# LurkerNanov20.net
KiCad netlist of a schematic drawn in EAGLE
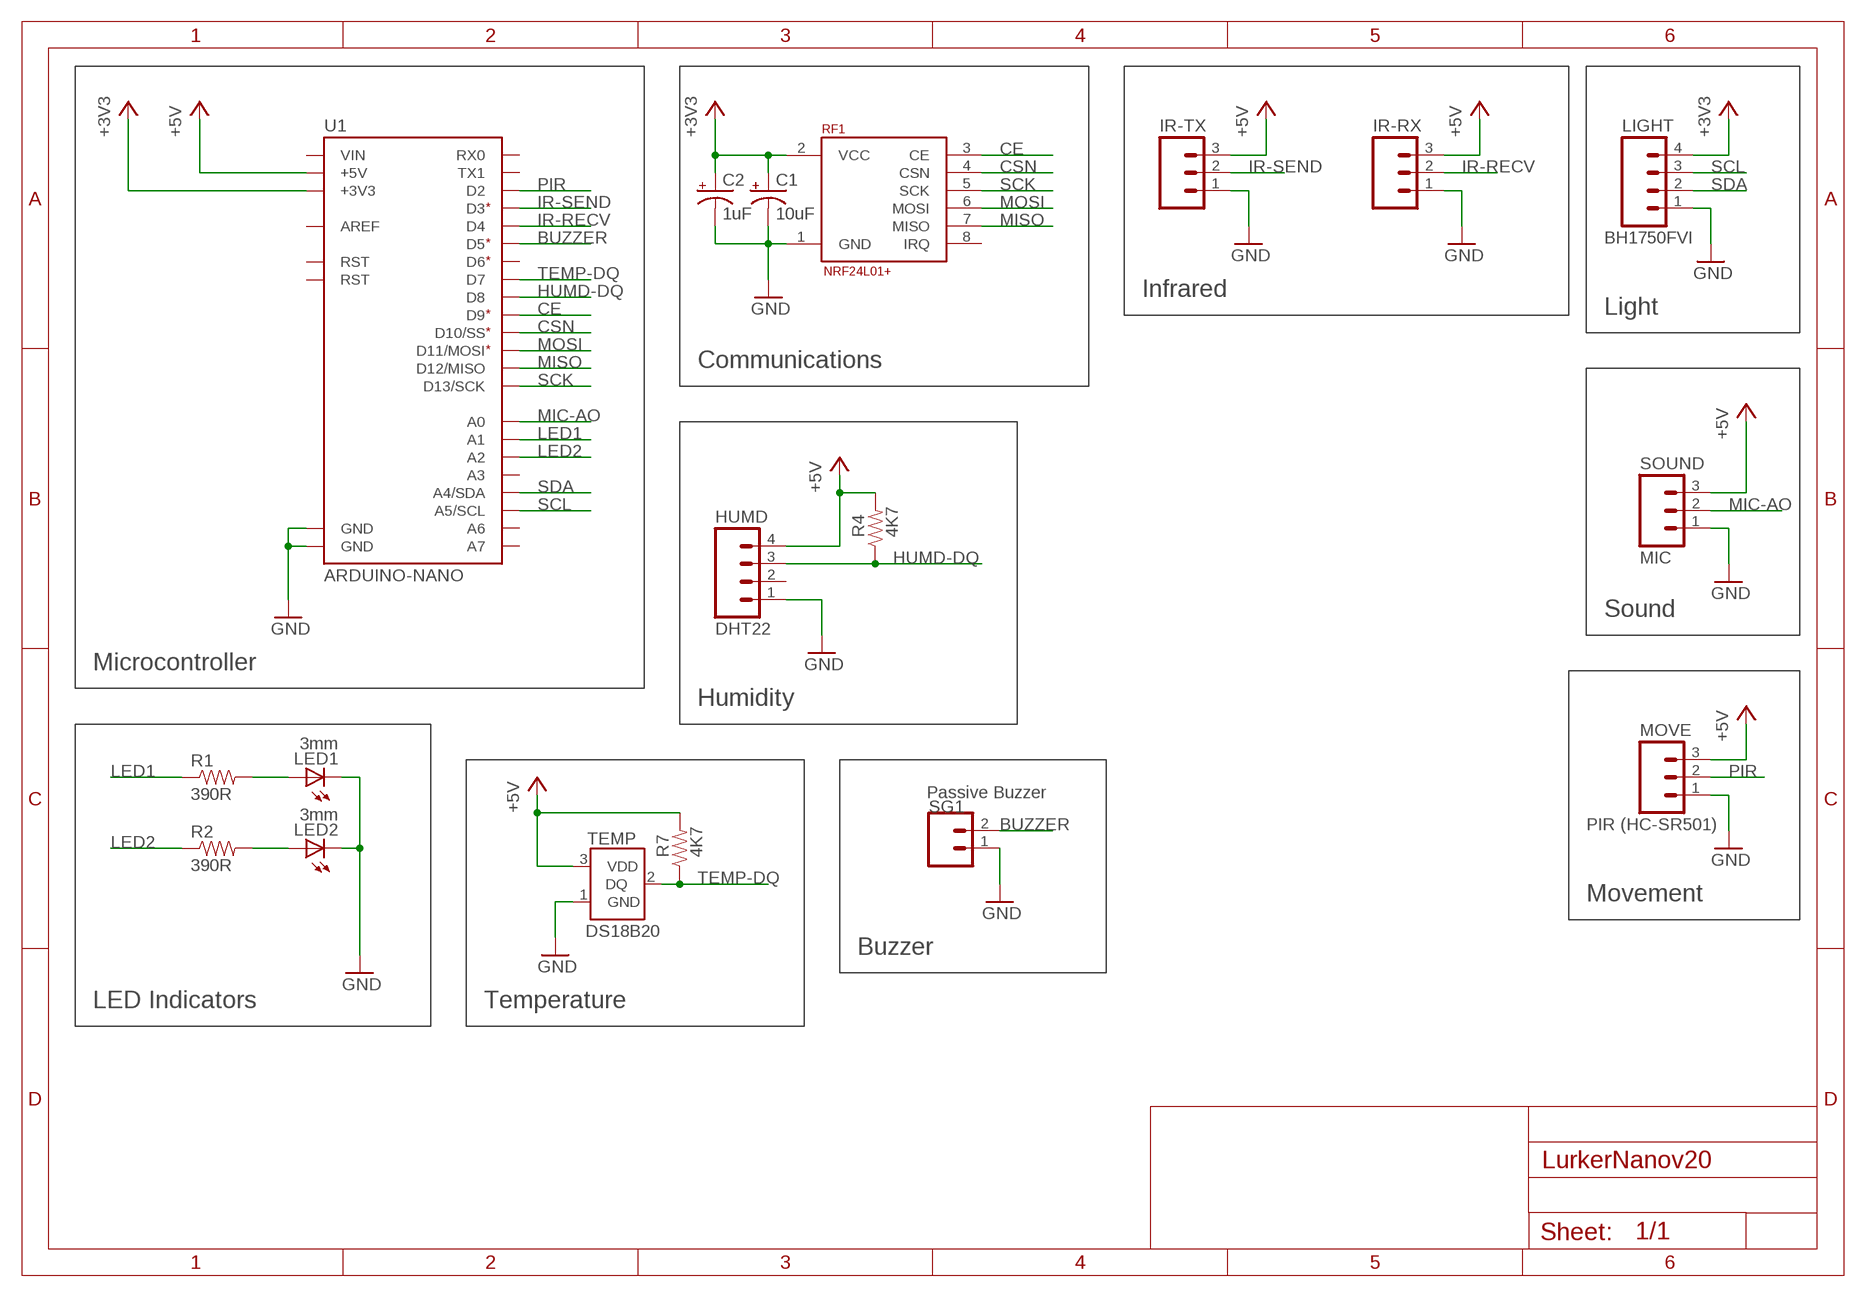
[diagram p0: schematic, sheet 1, part 1 of 2]
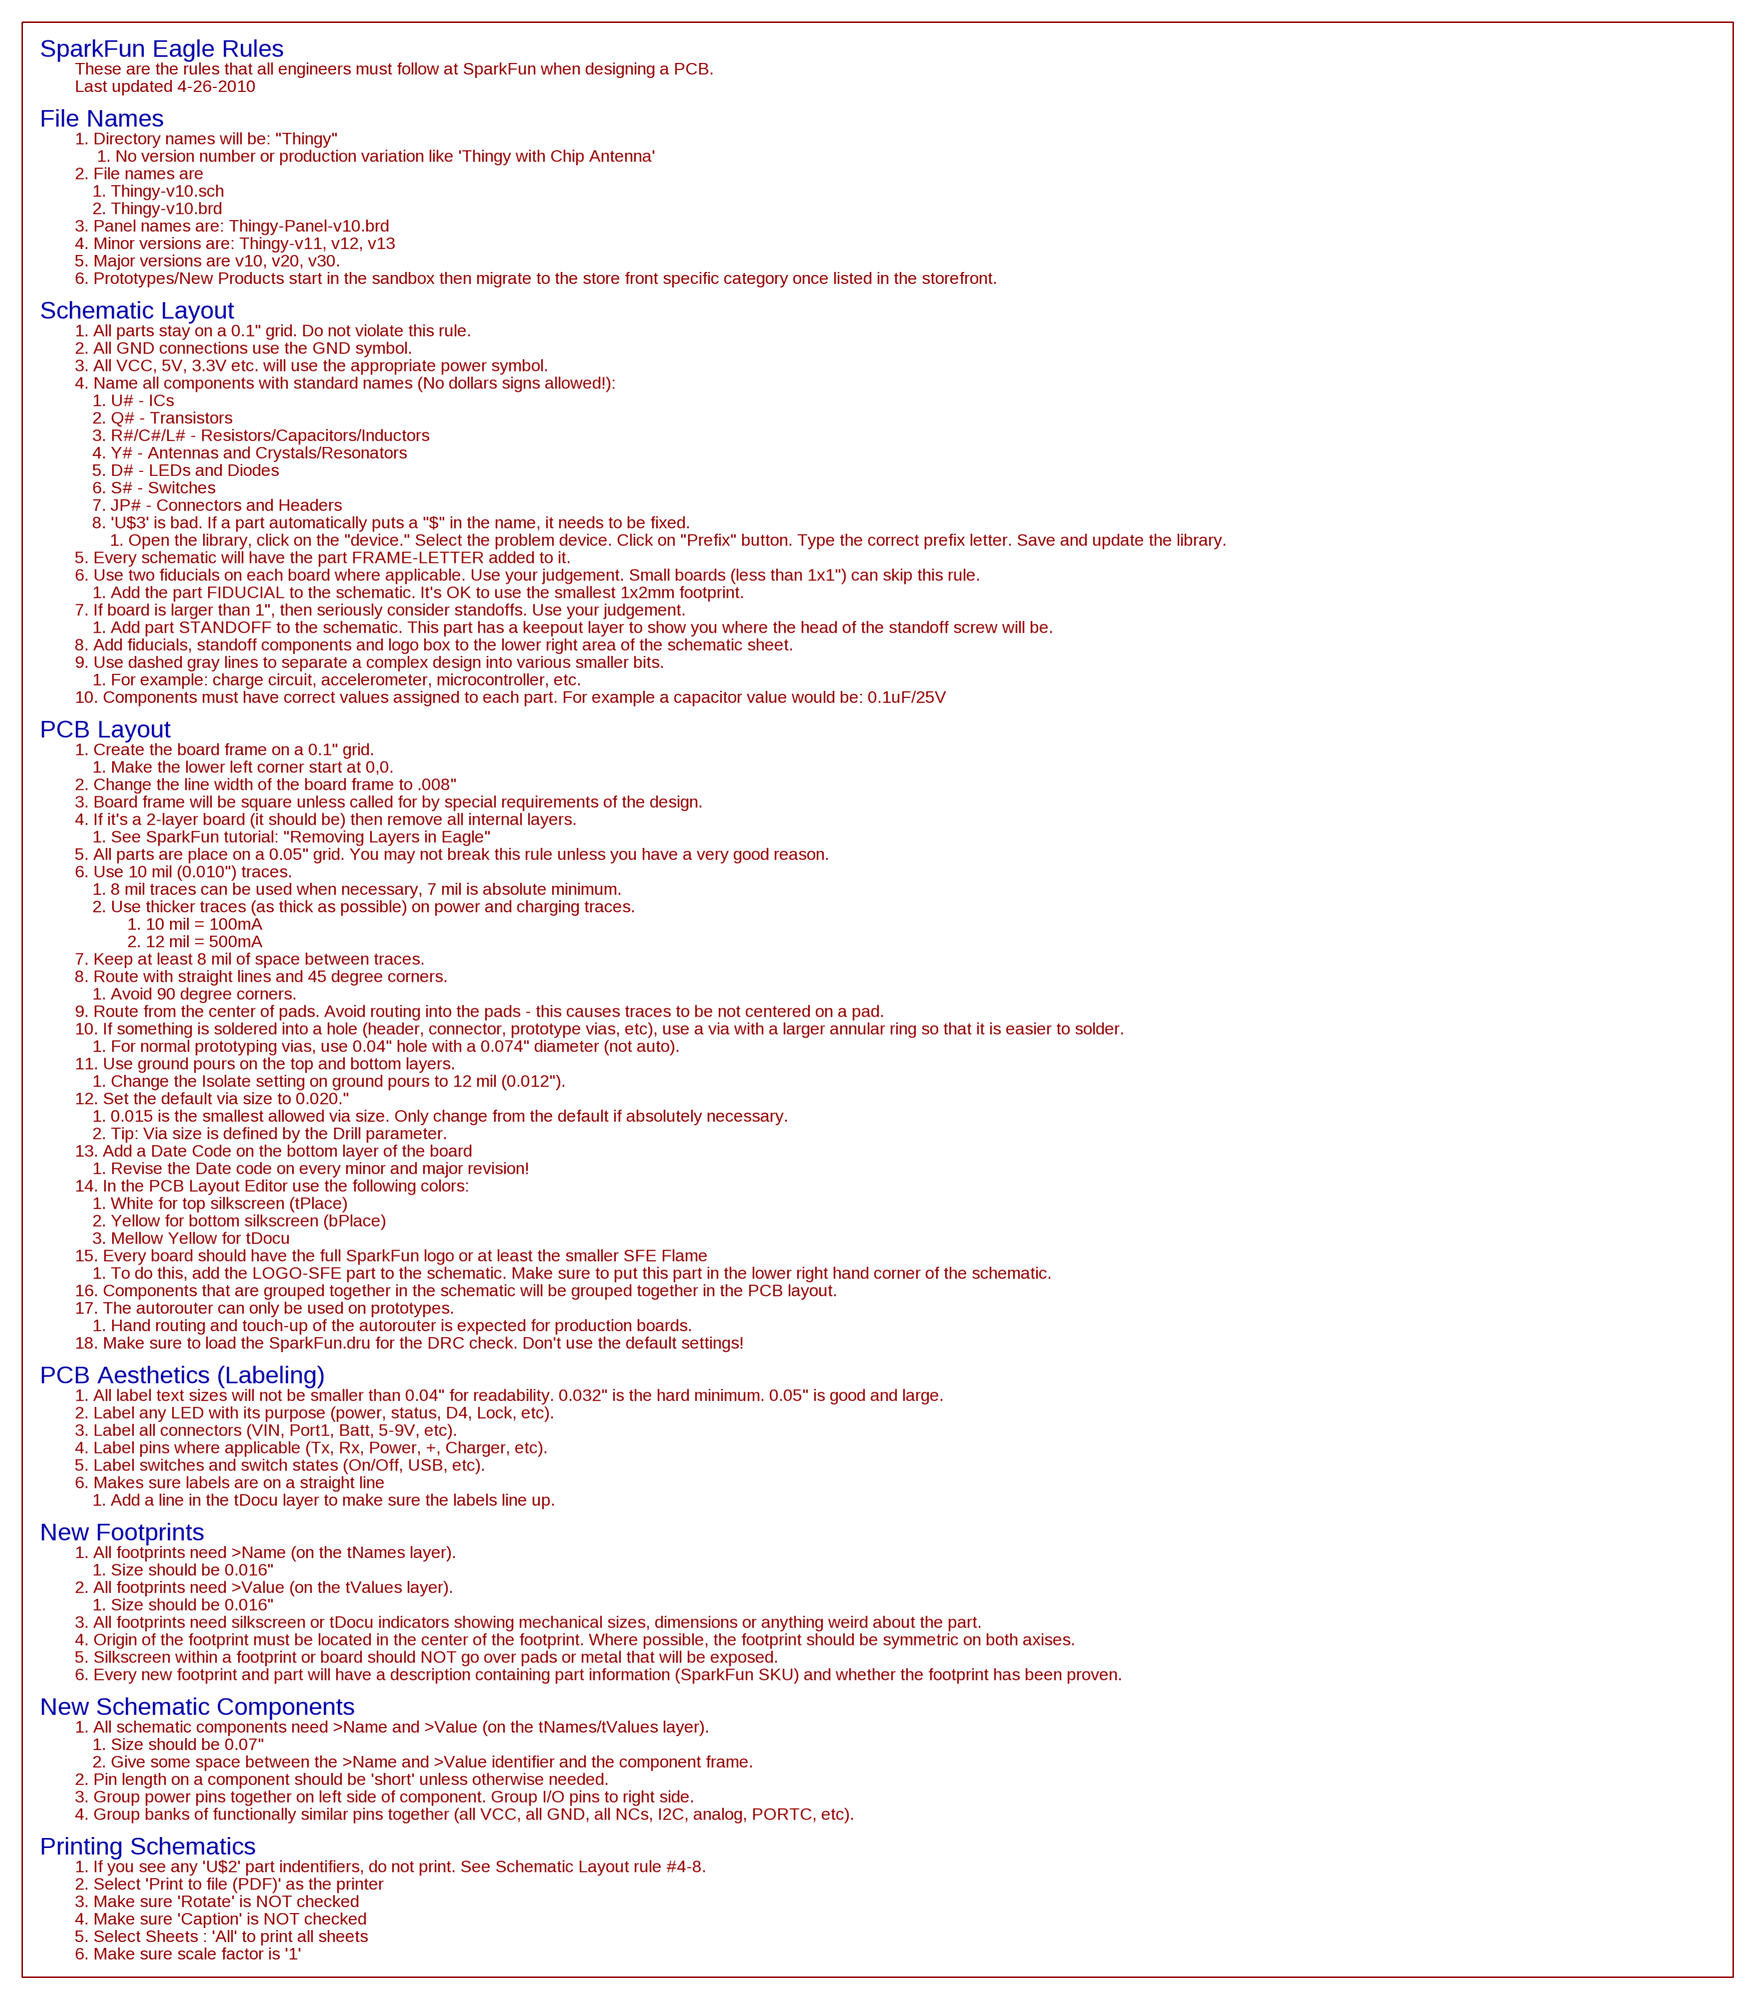
[diagram p1: schematic, sheet 1, part 2 of 2]

(export (version "E")
  (design (tool "Eeschema 10.0.6"))
  (components
    (comp (ref "C1")
      (value "10uF")
      (footprint "eagle-import:EIA3216")
      (libsource (lib "eagle-import") (part "CAP_POL1206"))
    )
    (comp (ref "C2")
      (value "1uF")
      (footprint "eagle-import:EIA3216")
      (libsource (lib "eagle-import") (part "CAP_POL1206"))
    )
    (comp (ref "HUMD")
      (value "DHT22")
      (footprint "eagle-import:1X04")
      (libsource (lib "eagle-import") (part "M04PTH"))
    )
    (comp (ref "IR-RX")
      (value "M03PTH")
      (footprint "eagle-import:1X03")
      (libsource (lib "eagle-import") (part "M03PTH"))
    )
    (comp (ref "IR-TX")
      (value "M03PTH")
      (footprint "eagle-import:1X03")
      (libsource (lib "eagle-import") (part "M03PTH"))
    )
    (comp (ref "LED1")
      (value "3mm")
      (footprint "eagle-import:LED3MM")
      (libsource (lib "eagle-import") (part "LED3MM"))
    )
    (comp (ref "LED2")
      (value "3mm")
      (footprint "eagle-import:LED3MM")
      (libsource (lib "eagle-import") (part "LED3MM"))
    )
    (comp (ref "LIGHT")
      (value "BH1750FVI")
      (footprint "eagle-import:1X04")
      (libsource (lib "eagle-import") (part "M04PTH"))
    )
    (comp (ref "MOVE")
      (value "PIR (HC-SR501)")
      (footprint "eagle-import:1X03")
      (libsource (lib "eagle-import") (part "M03PTH"))
    )
    (comp (ref "R1")
      (value "390R")
      (footprint "eagle-import:1206")
      (libsource (lib "eagle-import") (part "RESISTOR1206"))
    )
    (comp (ref "R2")
      (value "390R")
      (footprint "eagle-import:1206")
      (libsource (lib "eagle-import") (part "RESISTOR1206"))
    )
    (comp (ref "R4")
      (value "4K7")
      (footprint "eagle-import:1206")
      (libsource (lib "eagle-import") (part "RESISTOR1206"))
    )
    (comp (ref "R7")
      (value "4K7")
      (footprint "eagle-import:1206")
      (libsource (lib "eagle-import") (part "RESISTOR1206"))
    )
    (comp (ref "RF1")
      (value "NRF24L01+")
      (footprint "eagle-import:NRF24L01+-HEADER")
      (libsource (lib "eagle-import") (part "NRF24L01+"))
    )
    (comp (ref "SG1")
      (value "Passive Buzzer")
      (footprint "eagle-import:1X02")
      (libsource (lib "eagle-import") (part "M02PTH"))
    )
    (comp (ref "SOUND")
      (value "MIC")
      (footprint "eagle-import:1X03")
      (libsource (lib "eagle-import") (part "M03PTH"))
    )
    (comp (ref "TEMP")
      (value "DS18B20")
      (footprint "eagle-import:TO-92-AMMO")
      (libsource (lib "eagle-import") (part "DS18B20"))
    )
    (comp (ref "U1")
      (value "ARDUINO-NANO")
      (footprint "eagle-import:NANO-SHIELD")
      (libsource (lib "eagle-import") (part "ARDUINO-NANO"))
    )
  )
  (nets
    (net (code "1") (name "+3V3") (class "Default")
      (node (ref "C1") (pin "A") (pinfunction "+_A") (pintype "passive"))
      (node (ref "C2") (pin "A") (pinfunction "+_A") (pintype "passive"))
      (node (ref "LIGHT") (pin "4") (pinfunction "4_4") (pintype "passive"))
      (node (ref "RF1") (pin "2") (pinfunction "VCC_2") (pintype "power_in"))
      (node (ref "U1") (pin "3V3") (pinfunction "+3V3_3V3") (pintype "power_in"))
    )
    (net (code "2") (name "+5V") (class "Default")
      (node (ref "HUMD") (pin "4") (pinfunction "4_4") (pintype "passive"))
      (node (ref "IR-RX") (pin "3") (pinfunction "3_3") (pintype "passive"))
      (node (ref "IR-TX") (pin "3") (pinfunction "3_3") (pintype "passive"))
      (node (ref "MOVE") (pin "3") (pinfunction "3_3") (pintype "passive"))
      (node (ref "R4") (pin "2") (pinfunction "2_2") (pintype "passive"))
      (node (ref "R7") (pin "2") (pinfunction "2_2") (pintype "passive"))
      (node (ref "SOUND") (pin "3") (pinfunction "3_3") (pintype "passive"))
      (node (ref "TEMP") (pin "3") (pinfunction "VDD_3") (pintype "power_in"))
      (node (ref "U1") (pin "5V") (pinfunction "+5V_5V") (pintype "power_in"))
    )
    (net (code "3") (name "/BUZZER") (class "Default")
      (node (ref "SG1") (pin "2") (pinfunction "2_2") (pintype "passive"))
      (node (ref "U1") (pin "D5") (pinfunction "D5_D5") (pintype "bidirectional"))
    )
    (net (code "4") (name "/CE") (class "Default")
      (node (ref "RF1") (pin "3") (pinfunction "CE_3") (pintype "bidirectional"))
      (node (ref "U1") (pin "D9") (pinfunction "D9_D9") (pintype "bidirectional"))
    )
    (net (code "5") (name "/CSN") (class "Default")
      (node (ref "RF1") (pin "4") (pinfunction "CSN_4") (pintype "bidirectional"))
      (node (ref "U1") (pin "D10") (pinfunction "D10/SS_D10") (pintype "bidirectional"))
    )
    (net (code "6") (name "/HUMD-DQ") (class "Default")
      (node (ref "HUMD") (pin "3") (pinfunction "3_3") (pintype "passive"))
      (node (ref "R4") (pin "1") (pinfunction "1_1") (pintype "passive"))
      (node (ref "U1") (pin "D8") (pinfunction "D8_D8") (pintype "bidirectional"))
    )
    (net (code "7") (name "/IR-RECV") (class "Default")
      (node (ref "IR-RX") (pin "2") (pinfunction "2_2") (pintype "passive"))
      (node (ref "U1") (pin "D4") (pinfunction "D4_D4") (pintype "bidirectional"))
    )
    (net (code "8") (name "/IR-SEND") (class "Default")
      (node (ref "IR-TX") (pin "2") (pinfunction "2_2") (pintype "passive"))
      (node (ref "U1") (pin "D3") (pinfunction "D3_D3") (pintype "bidirectional"))
    )
    (net (code "9") (name "/LED1") (class "Default")
      (node (ref "R1") (pin "1") (pinfunction "1_1") (pintype "passive"))
      (node (ref "U1") (pin "A1") (pinfunction "A1_A1") (pintype "bidirectional"))
    )
    (net (code "10") (name "/LED2") (class "Default")
      (node (ref "R2") (pin "1") (pinfunction "1_1") (pintype "passive"))
      (node (ref "U1") (pin "A2") (pinfunction "A2_A2") (pintype "bidirectional"))
    )
    (net (code "11") (name "/MIC-AO") (class "Default")
      (node (ref "SOUND") (pin "2") (pinfunction "2_2") (pintype "passive"))
      (node (ref "U1") (pin "A0") (pinfunction "A0_A0") (pintype "bidirectional"))
    )
    (net (code "12") (name "/MISO") (class "Default")
      (node (ref "RF1") (pin "7") (pinfunction "MISO_7") (pintype "bidirectional"))
      (node (ref "U1") (pin "D12") (pinfunction "D12/MISO_D12") (pintype "bidirectional"))
    )
    (net (code "13") (name "/MOSI") (class "Default")
      (node (ref "RF1") (pin "6") (pinfunction "MOSI_6") (pintype "bidirectional"))
      (node (ref "U1") (pin "D11") (pinfunction "D11/MOSI_D11") (pintype "bidirectional"))
    )
    (net (code "14") (name "/PIR") (class "Default")
      (node (ref "MOVE") (pin "2") (pinfunction "2_2") (pintype "passive"))
      (node (ref "U1") (pin "D2") (pinfunction "D2_D2") (pintype "bidirectional"))
    )
    (net (code "15") (name "/SCK") (class "Default")
      (node (ref "RF1") (pin "5") (pinfunction "SCK_5") (pintype "bidirectional"))
      (node (ref "U1") (pin "D13") (pinfunction "D13/SCK_D13") (pintype "bidirectional"))
    )
    (net (code "16") (name "/SCL") (class "Default")
      (node (ref "LIGHT") (pin "3") (pinfunction "3_3") (pintype "passive"))
      (node (ref "U1") (pin "A5") (pinfunction "A5/SCL_A5") (pintype "bidirectional"))
    )
    (net (code "17") (name "/SDA") (class "Default")
      (node (ref "LIGHT") (pin "2") (pinfunction "2_2") (pintype "passive"))
      (node (ref "U1") (pin "A4") (pinfunction "A4/SDA_A4") (pintype "bidirectional"))
    )
    (net (code "18") (name "/TEMP-DQ") (class "Default")
      (node (ref "R7") (pin "1") (pinfunction "1_1") (pintype "passive"))
      (node (ref "TEMP") (pin "2") (pinfunction "DQ_2") (pintype "bidirectional"))
      (node (ref "U1") (pin "D7") (pinfunction "D7_D7") (pintype "bidirectional"))
    )
    (net (code "19") (name "/VIN") (class "Default")
      (node (ref "U1") (pin "VIN") (pinfunction "VIN_VIN") (pintype "power_in"))
    )
    (net (code "20") (name "GND") (class "Default")
      (node (ref "C1") (pin "C") (pinfunction "-_C") (pintype "passive"))
      (node (ref "C2") (pin "C") (pinfunction "-_C") (pintype "passive"))
      (node (ref "HUMD") (pin "1") (pinfunction "1_1") (pintype "passive"))
      (node (ref "IR-RX") (pin "1") (pinfunction "1_1") (pintype "passive"))
      (node (ref "IR-TX") (pin "1") (pinfunction "1_1") (pintype "passive"))
      (node (ref "LED1") (pin "K") (pinfunction "C_K") (pintype "passive"))
      (node (ref "LED2") (pin "K") (pinfunction "C_K") (pintype "passive"))
      (node (ref "LIGHT") (pin "1") (pinfunction "1_1") (pintype "passive"))
      (node (ref "MOVE") (pin "1") (pinfunction "1_1") (pintype "passive"))
      (node (ref "RF1") (pin "1") (pinfunction "GND_1") (pintype "power_in"))
      (node (ref "SG1") (pin "1") (pinfunction "1_1") (pintype "passive"))
      (node (ref "SOUND") (pin "1") (pinfunction "1_1") (pintype "passive"))
      (node (ref "TEMP") (pin "1") (pinfunction "GND_1") (pintype "power_in"))
      (node (ref "U1") (pin "GND@0") (pinfunction "GND_GND@0") (pintype "power_in"))
      (node (ref "U1") (pin "GND@1") (pinfunction "GND_GND@1") (pintype "power_in"))
    )
    (net (code "21") (name "Net-(LED1-PadA)") (class "Default")
      (node (ref "LED1") (pin "A") (pinfunction "A_A") (pintype "passive"))
      (node (ref "R1") (pin "2") (pinfunction "2_2") (pintype "passive"))
    )
    (net (code "22") (name "Net-(LED2-PadA)") (class "Default")
      (node (ref "LED2") (pin "A") (pinfunction "A_A") (pintype "passive"))
      (node (ref "R2") (pin "2") (pinfunction "2_2") (pintype "passive"))
    )
    (net (code "23") (name "unconnected-(HUMD-Pad2)") (class "Default")
      (node (ref "HUMD") (pin "2") (pinfunction "2_2") (pintype "passive"))
    )
    (net (code "24") (name "unconnected-(RF1-IRQ-Pad8)") (class "Default")
      (node (ref "RF1") (pin "8") (pinfunction "IRQ_8") (pintype "bidirectional"))
    )
    (net (code "25") (name "unconnected-(U1-AREF-PadREF)") (class "Default")
      (node (ref "U1") (pin "REF") (pinfunction "AREF_REF") (pintype "output"))
    )
    (net (code "26") (name "unconnected-(U1-PadA3)") (class "Default")
      (node (ref "U1") (pin "A3") (pinfunction "A3_A3") (pintype "bidirectional"))
    )
    (net (code "27") (name "unconnected-(U1-PadA6)") (class "Default")
      (node (ref "U1") (pin "A6") (pinfunction "A6_A6") (pintype "bidirectional"))
    )
    (net (code "28") (name "unconnected-(U1-PadA7)") (class "Default")
      (node (ref "U1") (pin "A7") (pinfunction "A7_A7") (pintype "bidirectional"))
    )
    (net (code "29") (name "unconnected-(U1-PadD6)") (class "Default")
      (node (ref "U1") (pin "D6") (pinfunction "D6_D6") (pintype "bidirectional"))
    )
    (net (code "30") (name "unconnected-(U1-PadRST)") (class "Default")
      (node (ref "U1") (pin "RST") (pinfunction "RST_RST") (pintype "bidirectional"))
    )
    (net (code "31") (name "unconnected-(U1-RST-PadRST@0)") (class "Default")
      (node (ref "U1") (pin "RST@0") (pinfunction "RST_RST@0") (pintype "bidirectional"))
    )
    (net (code "32") (name "unconnected-(U1-RX0-PadRX)") (class "Default")
      (node (ref "U1") (pin "RX") (pinfunction "RX0_RX") (pintype "bidirectional"))
    )
    (net (code "33") (name "unconnected-(U1-TX1-PadTX)") (class "Default")
      (node (ref "U1") (pin "TX") (pinfunction "TX1_TX") (pintype "bidirectional"))
    )
  )
)
